# Single_Item_Sensor.net
KiCad netlist of a schematic drawn in EAGLE
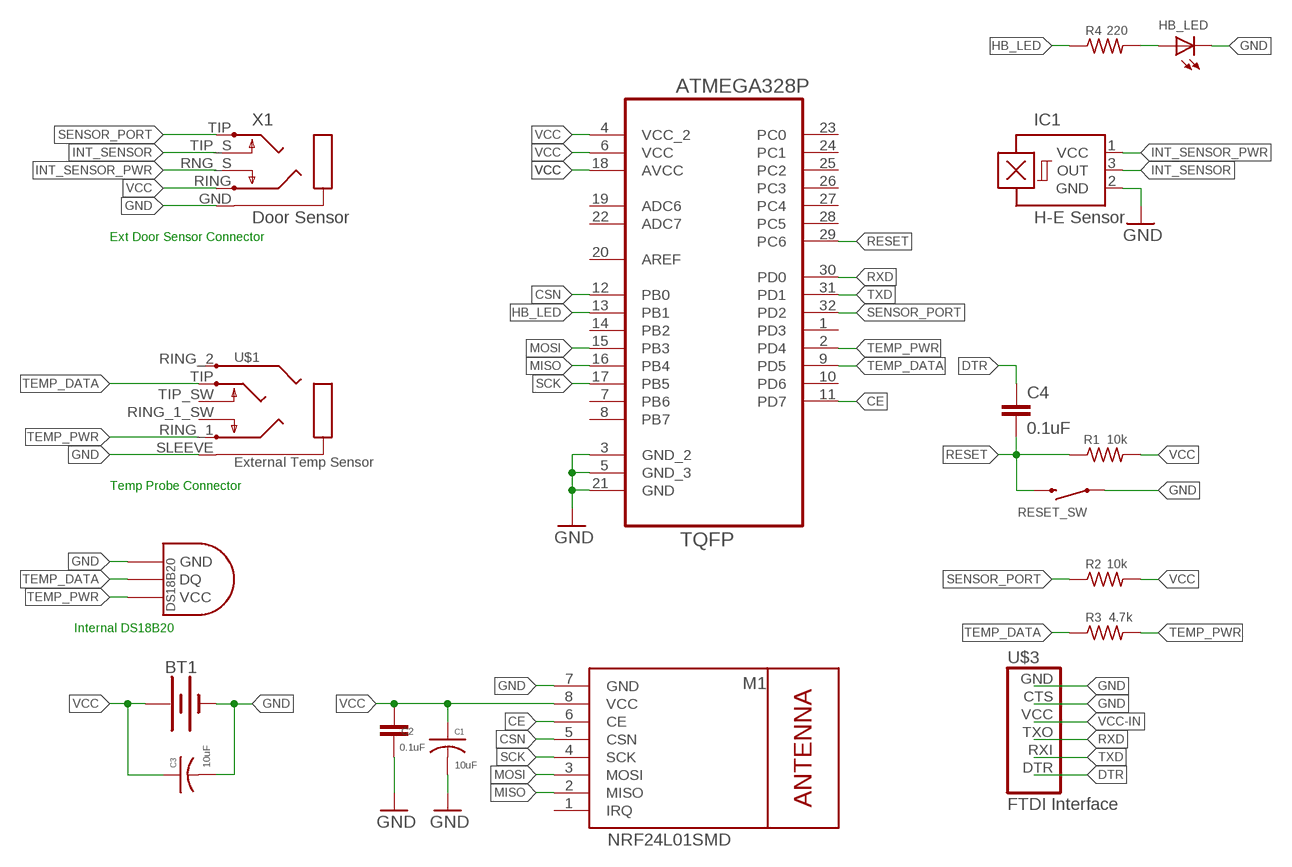
[diagram p0: schematic, sheet 1]

(export (version "E")
  (design (tool "Eeschema 10.0.6"))
  (components
    (comp (ref "BT1")
      (value "BATTERY-20MM_SMD_4LEGS")
      (footprint "eagle-import:BATTCON_20MM_4LEGS")
      (libsource (lib "eagle-import") (part "BATTERY-20MM_SMD_4LEGS"))
    )
    (comp (ref "C1")
      (value "10uF")
      (footprint "eagle-import:C1206")
      (libsource (lib "eagle-import") (part "C-USC1206"))
    )
    (comp (ref "C2")
      (value "0.1uF")
      (footprint "eagle-import:1206")
      (libsource (lib "eagle-import") (part "CAP1206"))
    )
    (comp (ref "C3")
      (value "10uF")
      (footprint "eagle-import:C1206")
      (libsource (lib "eagle-import") (part "C-USC1206"))
    )
    (comp (ref "C4")
      (value "0.1uF")
      (footprint "eagle-import:1206")
      (libsource (lib "eagle-import") (part "CAP1206"))
    )
    (comp (ref "HB_LED")
      (value "LEDCHIP-LED0603")
      (footprint "eagle-import:CHIP-LED0603")
      (libsource (lib "eagle-import") (part "LEDCHIP-LED0603"))
    )
    (comp (ref "IC1")
      (value "H-E Sensor")
      (footprint "eagle-import:SIP3-UA")
      (libsource (lib "eagle-import") (part "A12?UA02"))
    )
    (comp (ref "M1")
      (value "NRF24L01SMD")
      (footprint "eagle-import:WIRELESS-NRF24L01-SMD")
      (libsource (lib "eagle-import") (part "WIRELESS-NRF24L01SMD"))
    )
    (comp (ref "R1")
      (value "10k")
      (footprint "eagle-import:M1206")
      (libsource (lib "eagle-import") (part "R-US_M1206"))
    )
    (comp (ref "R2")
      (value "10k")
      (footprint "eagle-import:M1206")
      (libsource (lib "eagle-import") (part "R-US_M1206"))
    )
    (comp (ref "R3")
      (value "4.7k")
      (footprint "eagle-import:M1206")
      (libsource (lib "eagle-import") (part "R-US_M1206"))
    )
    (comp (ref "R4")
      (value "220")
      (footprint "eagle-import:M1206")
      (libsource (lib "eagle-import") (part "R-US_M1206"))
    )
    (comp (ref "RESET_SW")
      (value "SWITCH-MOMENTARY-2-SMD-1101NE")
      (footprint "eagle-import:TACTILE-SWITCH-1101NE")
      (libsource (lib "eagle-import") (part "SWITCH-MOMENTARY-2-SMD-1101NE"))
    )
    (comp (ref "U$1")
      (value "External Temp Sensor")
      (footprint "eagle-import:PJ-242")
      (libsource (lib "eagle-import") (part "PJ-242"))
    )
    (comp (ref "U$2")
      (value "DS1820TO92")
      (footprint "eagle-import:DS1820")
      (libsource (lib "eagle-import") (part "DS1820TO92"))
    )
    (comp (ref "U$3")
      (value "FTDI Interface")
      (footprint "eagle-import:1X6-FTDI")
      (libsource (lib "eagle-import") (part "FTDI-HEADER"))
    )
    (comp (ref "U1")
      (value "ATMEGA328P-AU")
      (footprint "eagle-import:QFP80P900X900X120-32N")
      (libsource (lib "eagle-import") (part "ATMEGA328P-AU"))
    )
    (comp (ref "X1")
      (value "Door Sensor")
      (footprint "eagle-import:PG203J")
      (libsource (lib "eagle-import") (part "PG203JPJ-328"))
    )
  )
  (nets
    (net (code "1") (name "CE") (class "Default")
      (node (ref "M1") (pin "6") (pinfunction "CE_6") (pintype "bidirectional"))
      (node (ref "U1") (pin "11") (pinfunction "PD7_11") (pintype "bidirectional"))
    )
    (net (code "2") (name "CSN") (class "Default")
      (node (ref "M1") (pin "5") (pinfunction "CSN_5") (pintype "bidirectional"))
      (node (ref "U1") (pin "12") (pinfunction "PB0_12") (pintype "bidirectional"))
    )
    (net (code "3") (name "DTR") (class "Default")
      (node (ref "C4") (pin "1") (pinfunction "1_1") (pintype "passive"))
      (node (ref "U$3") (pin "DTR") (pinfunction "DTR_DTR") (pintype "passive"))
    )
    (net (code "4") (name "GND") (class "Default")
      (node (ref "BT1") (pin "NEGATIVE") (pinfunction "-_NEGATIVE") (pintype "power_in"))
      (node (ref "C1") (pin "2") (pinfunction "2_2") (pintype "passive"))
      (node (ref "C2") (pin "2") (pinfunction "2_2") (pintype "passive"))
      (node (ref "C3") (pin "2") (pinfunction "2_2") (pintype "passive"))
      (node (ref "HB_LED") (pin "C") (pinfunction "C_C") (pintype "passive"))
      (node (ref "IC1") (pin "2") (pinfunction "GND_2") (pintype "power_in"))
      (node (ref "M1") (pin "7") (pinfunction "GND_7") (pintype "power_in"))
      (node (ref "RESET_SW") (pin "P$1") (pinfunction "1_P$1") (pintype "passive"))
      (node (ref "U$1") (pin "SLEEVE") (pinfunction "5_SLEEVE") (pintype "passive"))
      (node (ref "U$2") (pin "GND") (pinfunction "GND_GND") (pintype "power_in"))
      (node (ref "U$3") (pin "CTS") (pinfunction "CTS_CTS") (pintype "passive"))
      (node (ref "U$3") (pin "GND") (pinfunction "GND_GND") (pintype "passive"))
      (node (ref "U1") (pin "21") (pinfunction "GND_21") (pintype "passive"))
      (node (ref "U1") (pin "3") (pinfunction "GND_2_3") (pintype "passive"))
      (node (ref "U1") (pin "5") (pinfunction "GND_3_5") (pintype "passive"))
      (node (ref "X1") (pin "GND") (pinfunction "1_GND") (pintype "passive"))
    )
    (net (code "5") (name "HB_LED") (class "Default")
      (node (ref "R4") (pin "1") (pinfunction "1_1") (pintype "passive"))
      (node (ref "U1") (pin "13") (pinfunction "PB1_13") (pintype "bidirectional"))
    )
    (net (code "6") (name "INT_SENSOR") (class "Default")
      (node (ref "IC1") (pin "3") (pinfunction "OUT_3") (pintype "output"))
      (node (ref "X1") (pin "TIP_S") (pinfunction "4_TIP_S") (pintype "passive"))
    )
    (net (code "7") (name "INT_SENSOR_PWR") (class "Default")
      (node (ref "IC1") (pin "1") (pinfunction "VCC_1") (pintype "power_in"))
      (node (ref "X1") (pin "RNG_S") (pinfunction "3_RNG_S") (pintype "passive"))
    )
    (net (code "8") (name "MISO") (class "Default")
      (node (ref "M1") (pin "2") (pinfunction "MISO_2") (pintype "bidirectional"))
      (node (ref "U1") (pin "16") (pinfunction "PB4_16") (pintype "bidirectional"))
    )
    (net (code "9") (name "MOSI") (class "Default")
      (node (ref "M1") (pin "3") (pinfunction "MOSI_3") (pintype "bidirectional"))
      (node (ref "U1") (pin "15") (pinfunction "PB3_15") (pintype "bidirectional"))
    )
    (net (code "10") (name "Net-(HB_LED-PadA)") (class "Default")
      (node (ref "HB_LED") (pin "A") (pinfunction "A_A") (pintype "passive"))
      (node (ref "R4") (pin "2") (pinfunction "2_2") (pintype "passive"))
    )
    (net (code "11") (name "RESET") (class "Default")
      (node (ref "C4") (pin "2") (pinfunction "2_2") (pintype "passive"))
      (node (ref "R1") (pin "1") (pinfunction "1_1") (pintype "passive"))
      (node (ref "RESET_SW") (pin "P$2") (pinfunction "2_P$2") (pintype "passive"))
      (node (ref "U1") (pin "29") (pinfunction "PC6_29") (pintype "bidirectional"))
    )
    (net (code "12") (name "RXD") (class "Default")
      (node (ref "U$3") (pin "TXO") (pinfunction "TXO_TXO") (pintype "passive"))
      (node (ref "U1") (pin "30") (pinfunction "PD0_30") (pintype "bidirectional"))
    )
    (net (code "13") (name "SCK") (class "Default")
      (node (ref "M1") (pin "4") (pinfunction "SCK_4") (pintype "bidirectional"))
      (node (ref "U1") (pin "17") (pinfunction "PB5_17") (pintype "bidirectional"))
    )
    (net (code "14") (name "SENSOR_PORT") (class "Default")
      (node (ref "R2") (pin "1") (pinfunction "1_1") (pintype "passive"))
      (node (ref "U1") (pin "32") (pinfunction "PD2_32") (pintype "bidirectional"))
      (node (ref "X1") (pin "TIP") (pinfunction "5_TIP") (pintype "passive"))
    )
    (net (code "15") (name "TEMP_DATA") (class "Default")
      (node (ref "R3") (pin "1") (pinfunction "1_1") (pintype "passive"))
      (node (ref "U$1") (pin "TIP") (pinfunction "6_TIP") (pintype "passive"))
      (node (ref "U$2") (pin "DQ") (pinfunction "DQ_DQ") (pintype "bidirectional"))
      (node (ref "U1") (pin "9") (pinfunction "PD5_9") (pintype "bidirectional"))
    )
    (net (code "16") (name "TEMP_PWR") (class "Default")
      (node (ref "R3") (pin "2") (pinfunction "2_2") (pintype "passive"))
      (node (ref "U$1") (pin "RING_1") (pinfunction "3_RING_1") (pintype "passive"))
      (node (ref "U$2") (pin "VDD") (pinfunction "VCC_VDD") (pintype "power_in"))
      (node (ref "U1") (pin "2") (pinfunction "PD4_2") (pintype "bidirectional"))
    )
    (net (code "17") (name "TXD") (class "Default")
      (node (ref "U$3") (pin "RXI") (pinfunction "RXI_RXI") (pintype "passive"))
      (node (ref "U1") (pin "31") (pinfunction "PD1_31") (pintype "bidirectional"))
    )
    (net (code "18") (name "VCC") (class "Default")
      (node (ref "BT1") (pin "POSITIVE@1") (pinfunction "+_POSITIVE@1") (pintype "power_in"))
      (node (ref "BT1") (pin "POSITIVE@2") (pinfunction "+_POSITIVE@2") (pintype "power_in"))
      (node (ref "BT1") (pin "POSITIVE@3") (pinfunction "+_POSITIVE@3") (pintype "power_in"))
      (node (ref "BT1") (pin "POSITIVE@4") (pinfunction "+_POSITIVE@4") (pintype "power_in"))
      (node (ref "C1") (pin "1") (pinfunction "1_1") (pintype "passive"))
      (node (ref "C2") (pin "1") (pinfunction "1_1") (pintype "passive"))
      (node (ref "C3") (pin "1") (pinfunction "1_1") (pintype "passive"))
      (node (ref "M1") (pin "8") (pinfunction "VCC_8") (pintype "power_in"))
      (node (ref "R1") (pin "2") (pinfunction "2_2") (pintype "passive"))
      (node (ref "R2") (pin "2") (pinfunction "2_2") (pintype "passive"))
      (node (ref "U1") (pin "18") (pinfunction "AVCC_18") (pintype "power_in"))
      (node (ref "U1") (pin "4") (pinfunction "VCC_2_4") (pintype "power_in"))
      (node (ref "U1") (pin "6") (pinfunction "VCC_6") (pintype "power_in"))
      (node (ref "X1") (pin "RING") (pinfunction "2_RING") (pintype "passive"))
    )
    (net (code "19") (name "VCC-IN") (class "Default")
      (node (ref "U$3") (pin "VCC") (pinfunction "VCC_VCC") (pintype "passive"))
    )
    (net (code "20") (name "unconnected-(M1-IRQ-Pad1)") (class "Default")
      (node (ref "M1") (pin "1") (pinfunction "IRQ_1") (pintype "bidirectional"))
    )
    (net (code "21") (name "unconnected-(U$1-2-PadRING_2)") (class "Default")
      (node (ref "U$1") (pin "RING_2") (pinfunction "2_RING_2") (pintype "passive"))
    )
    (net (code "22") (name "unconnected-(U$1-4-PadRING_1_SW)") (class "Default")
      (node (ref "U$1") (pin "RING_1_SW") (pinfunction "4_RING_1_SW") (pintype "passive"))
    )
    (net (code "23") (name "unconnected-(U$1-7-PadTIP_SW)") (class "Default")
      (node (ref "U$1") (pin "TIP_SW") (pinfunction "7_TIP_SW") (pintype "passive"))
    )
    (net (code "24") (name "unconnected-(U1-ADC6-Pad19)") (class "Default")
      (node (ref "U1") (pin "19") (pinfunction "ADC6_19") (pintype "input"))
    )
    (net (code "25") (name "unconnected-(U1-ADC7-Pad22)") (class "Default")
      (node (ref "U1") (pin "22") (pinfunction "ADC7_22") (pintype "input"))
    )
    (net (code "26") (name "unconnected-(U1-AREF-Pad20)") (class "Default")
      (node (ref "U1") (pin "20") (pinfunction "AREF_20") (pintype "input"))
    )
    (net (code "27") (name "unconnected-(U1-PB2-Pad14)") (class "Default")
      (node (ref "U1") (pin "14") (pinfunction "PB2_14") (pintype "bidirectional"))
    )
    (net (code "28") (name "unconnected-(U1-PB6-Pad7)") (class "Default")
      (node (ref "U1") (pin "7") (pinfunction "PB6_7") (pintype "bidirectional"))
    )
    (net (code "29") (name "unconnected-(U1-PB7-Pad8)") (class "Default")
      (node (ref "U1") (pin "8") (pinfunction "PB7_8") (pintype "bidirectional"))
    )
    (net (code "30") (name "unconnected-(U1-PC0-Pad23)") (class "Default")
      (node (ref "U1") (pin "23") (pinfunction "PC0_23") (pintype "bidirectional"))
    )
    (net (code "31") (name "unconnected-(U1-PC1-Pad24)") (class "Default")
      (node (ref "U1") (pin "24") (pinfunction "PC1_24") (pintype "bidirectional"))
    )
    (net (code "32") (name "unconnected-(U1-PC2-Pad25)") (class "Default")
      (node (ref "U1") (pin "25") (pinfunction "PC2_25") (pintype "bidirectional"))
    )
    (net (code "33") (name "unconnected-(U1-PC3-Pad26)") (class "Default")
      (node (ref "U1") (pin "26") (pinfunction "PC3_26") (pintype "bidirectional"))
    )
    (net (code "34") (name "unconnected-(U1-PC4-Pad27)") (class "Default")
      (node (ref "U1") (pin "27") (pinfunction "PC4_27") (pintype "bidirectional"))
    )
    (net (code "35") (name "unconnected-(U1-PC5-Pad28)") (class "Default")
      (node (ref "U1") (pin "28") (pinfunction "PC5_28") (pintype "bidirectional"))
    )
    (net (code "36") (name "unconnected-(U1-PD3-Pad1)") (class "Default")
      (node (ref "U1") (pin "1") (pinfunction "PD3_1") (pintype "bidirectional"))
    )
    (net (code "37") (name "unconnected-(U1-PD6-Pad10)") (class "Default")
      (node (ref "U1") (pin "10") (pinfunction "PD6_10") (pintype "bidirectional"))
    )
  )
)
